# Video.net
KiCad netlist of a schematic drawn in Altium Designer
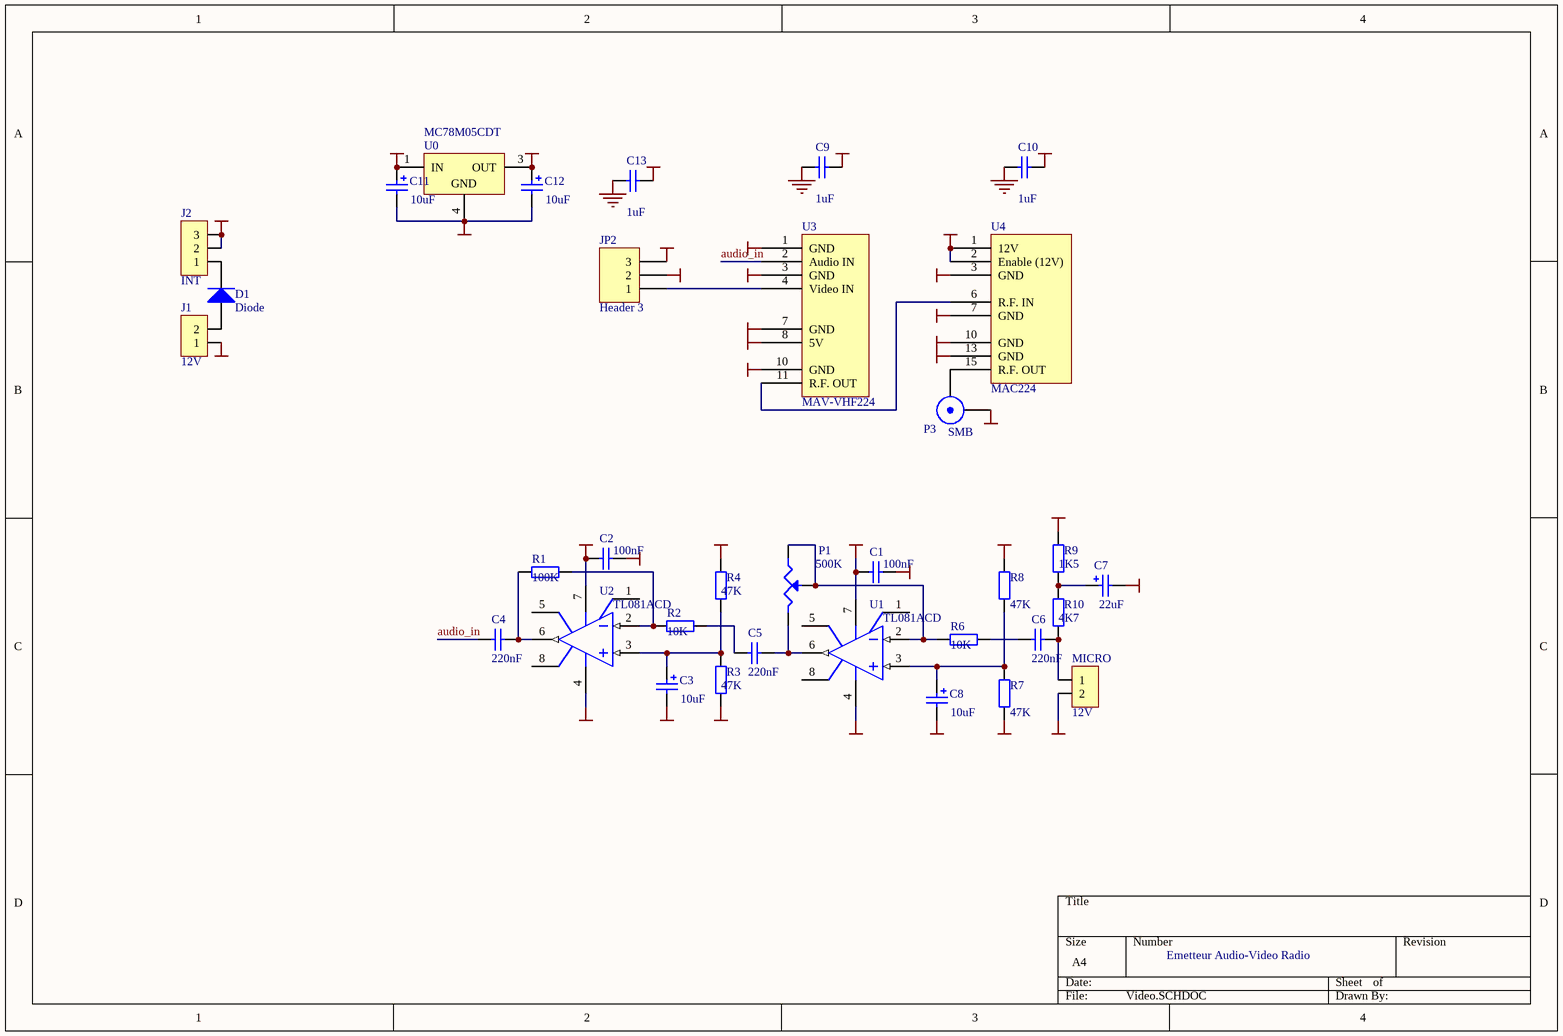
[diagram p0: Video.SCHDOC]

(export (version "E")
  (design (tool "Eeschema 10.0.6"))
  (components
    (comp (ref "C1")
      (value "100nF")
      (footprint "0805")
      (description "Capacitor")
      (fields (field (name "Comment") "Cap") (field (name "PUBLISHER") "Altium Limited"))
      (libsource (lib "Miscellaneous Devices") (part "Cap"))
    )
    (comp (ref "C2")
      (value "100nF")
      (footprint "1206")
      (description "Capacitor")
      (fields (field (name "Comment") "Cap") (field (name "PUBLISHER") "Altium Limited"))
      (libsource (lib "Miscellaneous Devices") (part "Cap"))
    )
    (comp (ref "C3")
      (value "10uF")
      (footprint "1206")
      (description "Polarized Capacitor (Radial)")
      (fields (field (name "Comment") "Cap Pol1") (field (name "PUBLISHER") "Altium Limited"))
      (libsource (lib "Miscellaneous Devices") (part "Cap Pol1"))
    )
    (comp (ref "C4")
      (value "220nF")
      (footprint "0805")
      (description "Capacitor")
      (fields (field (name "Comment") "Cap") (field (name "PUBLISHER") "Altium Limited"))
      (libsource (lib "Miscellaneous Devices") (part "Cap"))
    )
    (comp (ref "C5")
      (value "220nF")
      (footprint "0805")
      (description "Capacitor")
      (fields (field (name "Comment") "Cap") (field (name "PUBLISHER") "Altium Limited"))
      (libsource (lib "Miscellaneous Devices") (part "Cap"))
    )
    (comp (ref "C6")
      (value "220nF")
      (footprint "0805")
      (description "Capacitor")
      (fields (field (name "Comment") "Cap") (field (name "PUBLISHER") "Altium Limited"))
      (libsource (lib "Miscellaneous Devices") (part "Cap"))
    )
    (comp (ref "C7")
      (value "22uF")
      (footprint "1206")
      (description "Polarized Capacitor (Radial)")
      (fields (field (name "Comment") "Cap Pol1") (field (name "PUBLISHER") "Altium Limited"))
      (libsource (lib "Miscellaneous Devices") (part "Cap Pol1"))
    )
    (comp (ref "C8")
      (value "10uF")
      (footprint "1206")
      (description "Polarized Capacitor (Radial)")
      (fields (field (name "Comment") "Cap Pol1") (field (name "PUBLISHER") "Altium Limited"))
      (libsource (lib "Miscellaneous Devices") (part "Cap Pol1"))
    )
    (comp (ref "C9")
      (value "1uF")
      (footprint "1206")
      (description "Capacitor")
      (fields (field (name "Comment") "Cap") (field (name "PUBLISHER") "Altium Limited"))
      (libsource (lib "Miscellaneous Devices") (part "Cap"))
    )
    (comp (ref "C10")
      (value "1uF")
      (footprint "1206")
      (description "Capacitor")
      (fields (field (name "Comment") "Cap") (field (name "PUBLISHER") "Altium Limited"))
      (libsource (lib "Miscellaneous Devices") (part "Cap"))
    )
    (comp (ref "C11")
      (value "10uF")
      (footprint "1206")
      (description "Polarized Capacitor (Radial)")
      (fields (field (name "Comment") "Cap Pol1") (field (name "PUBLISHER") "Altium Limited"))
      (libsource (lib "Miscellaneous Devices") (part "Cap Pol1"))
    )
    (comp (ref "C12")
      (value "10uF")
      (footprint "1206")
      (description "Polarized Capacitor (Radial)")
      (fields (field (name "Comment") "Cap Pol1") (field (name "PUBLISHER") "Altium Limited"))
      (libsource (lib "Miscellaneous Devices") (part "Cap Pol1"))
    )
    (comp (ref "C13")
      (value "1uF")
      (footprint "1206")
      (description "Capacitor")
      (fields (field (name "Comment") "Cap") (field (name "PUBLISHER") "Altium Limited"))
      (libsource (lib "Miscellaneous Devices") (part "Cap"))
    )
    (comp (ref "D1")
      (value "Diode")
      (footprint "DSO-C2/X3.3")
      (description "Default Diode")
      (fields (field (name "PUBLISHER") "Altium Limited"))
      (libsource (lib "Miscellaneous Devices") (part "Diode"))
    )
    (comp (ref "J1") (value "12V") (footprint "CON2") (libsource (lib "") (part "CON2_1")))
    (comp (ref "J2") (value "INT") (footprint "TSIP3") (libsource (lib "*") (part "TCON3")))
    (comp (ref "JP2")
      (value "Header 3")
      (footprint "HDR1X3")
      (description "Header, 3-Pin")
      (fields (field (name "PUBLISHER") "Altium Limited"))
      (libsource (lib "Miscellaneous Connectors") (part "Header 3"))
    )
    (comp (ref "MICRO") (value "12V") (footprint "CON2") (libsource (lib "*") (part "CON2")))
    (comp (ref "P1")
      (value "500K")
      (footprint "VR4")
      (description "Potentiometre")
      (fields (field (name "Comment") "TPOT"))
      (libsource (lib "TOF") (part "TPOT"))
    )
    (comp (ref "P3")
      (value "SMB")
      (footprint "SMB_V-RJ45")
      (description "SMB Straight Connector")
      (fields (field (name "PUBLISHER") "Altium Limited"))
      (libsource (lib "Miscellaneous Connectors") (part "SMB"))
    )
    (comp (ref "R1")
      (value "100K")
      (footprint "0805")
      (description "Resistor")
      (fields (field (name "Comment") "Res2") (field (name "PUBLISHER") "Altium Limited"))
      (libsource (lib "") (part "Res2_1"))
    )
    (comp (ref "R2")
      (value "10K")
      (footprint "0805")
      (description "Resistor")
      (fields (field (name "Comment") "Res2") (field (name "PUBLISHER") "Altium Limited"))
      (libsource (lib "") (part "Res2_1"))
    )
    (comp (ref "R3")
      (value "47K")
      (footprint "0805")
      (description "Resistor")
      (fields (field (name "Comment") "Res2") (field (name "PUBLISHER") "Altium Limited"))
      (libsource (lib "Miscellaneous Devices") (part "Res2"))
    )
    (comp (ref "R4")
      (value "47K")
      (footprint "0805")
      (description "Resistor")
      (fields (field (name "Comment") "Res2") (field (name "PUBLISHER") "Altium Limited"))
      (libsource (lib "Miscellaneous Devices") (part "Res2"))
    )
    (comp (ref "R6")
      (value "10K")
      (footprint "0805")
      (description "Resistor")
      (fields (field (name "Comment") "Res2") (field (name "PUBLISHER") "Altium Limited"))
      (libsource (lib "") (part "Res2_1"))
    )
    (comp (ref "R7")
      (value "47K")
      (footprint "0805")
      (description "Resistor")
      (fields (field (name "Comment") "Res2") (field (name "PUBLISHER") "Altium Limited"))
      (libsource (lib "") (part "Res2_2"))
    )
    (comp (ref "R8")
      (value "47K")
      (footprint "0805")
      (description "Resistor")
      (fields (field (name "Comment") "Res2") (field (name "PUBLISHER") "Altium Limited"))
      (libsource (lib "Miscellaneous Devices") (part "Res2"))
    )
    (comp (ref "R9")
      (value "1K5")
      (footprint "0805")
      (description "Resistor")
      (fields (field (name "Comment") "Res2") (field (name "PUBLISHER") "Altium Limited"))
      (libsource (lib "Miscellaneous Devices") (part "Res2"))
    )
    (comp (ref "R10")
      (value "4K7")
      (footprint "0805")
      (description "Resistor")
      (fields (field (name "Comment") "Res2") (field (name "PUBLISHER") "Altium Limited"))
      (libsource (lib "Miscellaneous Devices") (part "Res2"))
    )
    (comp (ref "U0")
      (value "MC78M05CDT")
      (footprint "369A-03")
      (description "3-Terminal Medium-Current Positive Fixed Voltage Regulator")
      (fields (field (name "PUBLISHER") "Altium Limited"))
      (libsource (lib "Motorola Power Mgt Voltage Regulator") (part "MC78M05CDT"))
    )
    (comp (ref "U1")
      (value "TL081ACD")
      (footprint "751-02")
      (description "JFET-Input Operational Amplifier")
      (fields (field (name "PUBLISHER") "Altium Limited"))
      (libsource (lib "Motorola Amplifier Operational Amplifier") (part "TL081ACD"))
    )
    (comp (ref "U2")
      (value "TL081ACD")
      (footprint "751-02")
      (description "JFET-Input Operational Amplifier")
      (fields (field (name "PUBLISHER") "Altium Limited"))
      (libsource (lib "Motorola Amplifier Operational Amplifier") (part "TL081ACD"))
    )
    (comp (ref "U3")
      (value "MAV-VHF224")
      (footprint "MAV-VHF224")
      (libsource (lib "lebomb") (part "MAV-VHF224"))
    )
    (comp (ref "U4") (value "MAC224") (footprint "MCA224") (libsource (lib "lebomb") (part "MAC224")))
  )
  (nets
    (net (code "1") (name "/audio_in") (class "Default")
      (node (ref "C4") (pin "1") (pinfunction "1_1") (pintype "passive"))
      (node (ref "U3") (pin "2") (pinfunction "Audio_IN_2") (pintype "passive"))
    )
    (net (code "2") (name "5V") (class "Default")
      (node (ref "C12") (pin "1") (pinfunction "1_1") (pintype "passive"))
      (node (ref "C13") (pin "2") (pinfunction "2_2") (pintype "passive"))
      (node (ref "C9") (pin "2") (pinfunction "2_2") (pintype "passive"))
      (node (ref "JP2") (pin "3") (pinfunction "3_3") (pintype "passive"))
      (node (ref "U0") (pin "3") (pinfunction "OUT_3") (pintype "power_in"))
      (node (ref "U3") (pin "8") (pinfunction "5V_8") (pintype "passive"))
    )
    (net (code "3") (name "12V") (class "Default")
      (node (ref "C1") (pin "1") (pinfunction "1_1") (pintype "passive"))
      (node (ref "C10") (pin "2") (pinfunction "2_2") (pintype "passive"))
      (node (ref "C11") (pin "1") (pinfunction "1_1") (pintype "passive"))
      (node (ref "C2") (pin "1") (pinfunction "1_1") (pintype "passive"))
      (node (ref "J2") (pin "2") (pinfunction "2_2") (pintype "passive"))
      (node (ref "J2") (pin "3") (pinfunction "3_3") (pintype "passive"))
      (node (ref "R4") (pin "2") (pinfunction "2_2") (pintype "passive"))
      (node (ref "R8") (pin "2") (pinfunction "2_2") (pintype "passive"))
      (node (ref "R9") (pin "2") (pinfunction "2_2") (pintype "passive"))
      (node (ref "U0") (pin "1") (pinfunction "IN_1") (pintype "power_in"))
      (node (ref "U1") (pin "7") (pinfunction "V+_7") (pintype "power_in"))
      (node (ref "U2") (pin "7") (pinfunction "V+_7") (pintype "power_in"))
      (node (ref "U4") (pin "1") (pinfunction "12V_1") (pintype "passive"))
      (node (ref "U4") (pin "2") (pinfunction "Enable_(12V)_2") (pintype "passive"))
    )
    (net (code "4") (name "GND") (class "Default")
      (node (ref "C1") (pin "2") (pinfunction "2_2") (pintype "passive"))
      (node (ref "C10") (pin "1") (pinfunction "1_1") (pintype "passive"))
      (node (ref "C11") (pin "2") (pinfunction "2_2") (pintype "passive"))
      (node (ref "C12") (pin "2") (pinfunction "2_2") (pintype "passive"))
      (node (ref "C13") (pin "1") (pinfunction "1_1") (pintype "passive"))
      (node (ref "C2") (pin "2") (pinfunction "2_2") (pintype "passive"))
      (node (ref "C3") (pin "2") (pinfunction "2_2") (pintype "passive"))
      (node (ref "C7") (pin "2") (pinfunction "2_2") (pintype "passive"))
      (node (ref "C8") (pin "2") (pinfunction "2_2") (pintype "passive"))
      (node (ref "C9") (pin "1") (pinfunction "1_1") (pintype "passive"))
      (node (ref "J1") (pin "1") (pinfunction "1_1") (pintype "passive"))
      (node (ref "JP2") (pin "2") (pinfunction "2_2") (pintype "passive"))
      (node (ref "MICRO") (pin "2") (pinfunction "2_2") (pintype "passive"))
      (node (ref "P3") (pin "2") (pinfunction "Y_2") (pintype "passive"))
      (node (ref "R3") (pin "1") (pinfunction "1_1") (pintype "passive"))
      (node (ref "R7") (pin "2") (pinfunction "2_2") (pintype "passive"))
      (node (ref "U0") (pin "4") (pinfunction "GND_4") (pintype "power_in"))
      (node (ref "U1") (pin "4") (pinfunction "V-_4") (pintype "power_in"))
      (node (ref "U2") (pin "4") (pinfunction "V-_4") (pintype "power_in"))
      (node (ref "U3") (pin "1") (pinfunction "GND_1") (pintype "passive"))
      (node (ref "U3") (pin "10") (pinfunction "GND_10") (pintype "passive"))
      (node (ref "U3") (pin "3") (pinfunction "GND_3") (pintype "passive"))
      (node (ref "U3") (pin "7") (pinfunction "GND_7") (pintype "passive"))
      (node (ref "U4") (pin "10") (pinfunction "GND_10") (pintype "passive"))
      (node (ref "U4") (pin "13") (pinfunction "GND_13") (pintype "passive"))
      (node (ref "U4") (pin "3") (pinfunction "GND_3") (pintype "passive"))
      (node (ref "U4") (pin "7") (pinfunction "GND_7") (pintype "passive"))
    )
    (net (code "5") (name "Net-(C5-Pad1)") (class "Default")
      (node (ref "C5") (pin "1") (pinfunction "1_1") (pintype "passive"))
      (node (ref "R2") (pin "2") (pinfunction "2_2") (pintype "passive"))
    )
    (net (code "6") (name "Net-(C6-Pad1)") (class "Default")
      (node (ref "C6") (pin "1") (pinfunction "1_1") (pintype "passive"))
      (node (ref "R6") (pin "2") (pinfunction "2_2") (pintype "passive"))
    )
    (net (code "7") (name "Net-(C6-Pad2)") (class "Default")
      (node (ref "C6") (pin "2") (pinfunction "2_2") (pintype "passive"))
      (node (ref "MICRO") (pin "1") (pinfunction "1_1") (pintype "passive"))
      (node (ref "R10") (pin "1") (pinfunction "1_1") (pintype "passive"))
    )
    (net (code "8") (name "Net-(C7-Pad1)") (class "Default")
      (node (ref "C7") (pin "1") (pinfunction "1_1") (pintype "passive"))
      (node (ref "R10") (pin "2") (pinfunction "2_2") (pintype "passive"))
      (node (ref "R9") (pin "1") (pinfunction "1_1") (pintype "passive"))
    )
    (net (code "9") (name "Net-(D1-A)") (class "Default")
      (node (ref "D1") (pin "1") (pinfunction "A_1") (pintype "passive"))
      (node (ref "J1") (pin "2") (pinfunction "2_2") (pintype "passive"))
    )
    (net (code "10") (name "Net-(D1-K)") (class "Default")
      (node (ref "D1") (pin "2") (pinfunction "K_2") (pintype "passive"))
      (node (ref "J2") (pin "1") (pinfunction "1_1") (pintype "passive"))
    )
    (net (code "11") (name "Net-(P3-X)") (class "Default")
      (node (ref "P3") (pin "1") (pinfunction "X_1") (pintype "passive"))
      (node (ref "U4") (pin "15") (pinfunction "R.F._OUT_15") (pintype "passive"))
    )
    (net (code "12") (name "Net-(U1-IN+)") (class "Default")
      (node (ref "C8") (pin "1") (pinfunction "1_1") (pintype "passive"))
      (node (ref "R7") (pin "1") (pinfunction "1_1") (pintype "passive"))
      (node (ref "R8") (pin "1") (pinfunction "1_1") (pintype "passive"))
      (node (ref "U1") (pin "3") (pinfunction "IN+_3") (pintype "input"))
    )
    (net (code "13") (name "Net-(U1-IN-)") (class "Default")
      (node (ref "P1") (pin "1") (pintype "passive"))
      (node (ref "P1") (pin "2") (pintype "passive"))
      (node (ref "R6") (pin "1") (pinfunction "1_1") (pintype "passive"))
      (node (ref "U1") (pin "2") (pinfunction "IN-_2") (pintype "input"))
    )
    (net (code "14") (name "Net-(U1-OUT)") (class "Default")
      (node (ref "C5") (pin "2") (pinfunction "2_2") (pintype "passive"))
      (node (ref "P1") (pin "3") (pintype "passive"))
      (node (ref "U1") (pin "6") (pinfunction "OUT_6") (pintype "output"))
    )
    (net (code "15") (name "Net-(U2-IN+)") (class "Default")
      (node (ref "C3") (pin "1") (pinfunction "1_1") (pintype "passive"))
      (node (ref "R3") (pin "2") (pinfunction "2_2") (pintype "passive"))
      (node (ref "R4") (pin "1") (pinfunction "1_1") (pintype "passive"))
      (node (ref "U2") (pin "3") (pinfunction "IN+_3") (pintype "input"))
    )
    (net (code "16") (name "Net-(U2-IN-)") (class "Default")
      (node (ref "R1") (pin "2") (pinfunction "2_2") (pintype "passive"))
      (node (ref "R2") (pin "1") (pinfunction "1_1") (pintype "passive"))
      (node (ref "U2") (pin "2") (pinfunction "IN-_2") (pintype "input"))
    )
    (net (code "17") (name "Net-(U2-OUT)") (class "Default")
      (node (ref "C4") (pin "2") (pinfunction "2_2") (pintype "passive"))
      (node (ref "R1") (pin "1") (pinfunction "1_1") (pintype "passive"))
      (node (ref "U2") (pin "6") (pinfunction "OUT_6") (pintype "output"))
    )
    (net (code "18") (name "Net-(U3-R.F._OUT)") (class "Default")
      (node (ref "U3") (pin "11") (pinfunction "R.F._OUT_11") (pintype "passive"))
      (node (ref "U4") (pin "6") (pinfunction "R.F._IN_6") (pintype "passive"))
    )
    (net (code "19") (name "Net-(U3-Video_IN)") (class "Default")
      (node (ref "JP2") (pin "1") (pinfunction "1_1") (pintype "passive"))
      (node (ref "U3") (pin "4") (pinfunction "Video_IN_4") (pintype "passive"))
    )
    (net (code "20") (name "unconnected-(U1-NC-Pad8)") (class "Default")
      (node (ref "U1") (pin "8") (pinfunction "NC_8") (pintype "passive"))
    )
    (net (code "21") (name "unconnected-(U1-OS_NULL-Pad1)") (class "Default")
      (node (ref "U1") (pin "1") (pinfunction "OS_NULL_1") (pintype "passive"))
    )
    (net (code "22") (name "unconnected-(U1-OS_NULL-Pad5)") (class "Default")
      (node (ref "U1") (pin "5") (pinfunction "OS_NULL_5") (pintype "passive"))
    )
    (net (code "23") (name "unconnected-(U2-NC-Pad8)") (class "Default")
      (node (ref "U2") (pin "8") (pinfunction "NC_8") (pintype "passive"))
    )
    (net (code "24") (name "unconnected-(U2-OS_NULL-Pad1)") (class "Default")
      (node (ref "U2") (pin "1") (pinfunction "OS_NULL_1") (pintype "passive"))
    )
    (net (code "25") (name "unconnected-(U2-OS_NULL-Pad5)") (class "Default")
      (node (ref "U2") (pin "5") (pinfunction "OS_NULL_5") (pintype "passive"))
    )
  )
)
